# match.net
KiCad netlist of a schematic drawn in EAGLE
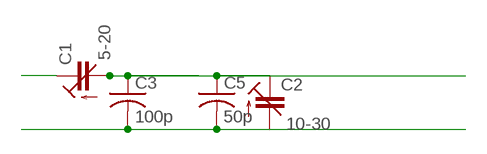
[diagram p0: schematic, sheet 1]

(export (version "E")
  (design (tool "Eeschema 10.0.6"))
  (components
    (comp (ref "C1")
      (value "5-20")
      (footprint "eagle-import:SGC3S")
      (libsource (lib "eagle-import") (part "C-TRIMM"))
    )
    (comp (ref "C2")
      (value "10-30")
      (footprint "eagle-import:SGC3S")
      (libsource (lib "eagle-import") (part "C-TRIMM"))
    )
    (comp (ref "C3")
      (value "100p")
      (footprint "eagle-import:C0805")
      (libsource (lib "eagle-import") (part "C-USC0805"))
    )
    (comp (ref "C5")
      (value "50p")
      (footprint "eagle-import:C0805")
      (libsource (lib "eagle-import") (part "C-USC0805"))
    )
  )
  (nets
    (net (code "1") (name "Net-(C1-A)") (class "Default")
      (node (ref "C1") (pin "P$1") (pinfunction "A_P$1") (pintype "passive"))
      (node (ref "C2") (pin "P$2") (pinfunction "E_P$2") (pintype "passive"))
      (node (ref "C3") (pin "1") (pinfunction "1_1") (pintype "passive"))
      (node (ref "C5") (pin "1") (pinfunction "1_1") (pintype "passive"))
    )
    (net (code "2") (name "Net-(C3-Pad2)") (class "Default")
      (node (ref "C3") (pin "2") (pinfunction "2_2") (pintype "passive"))
      (node (ref "C5") (pin "2") (pinfunction "2_2") (pintype "passive"))
    )
    (net (code "3") (name "unconnected-(C1-E-PadP$2)") (class "Default")
      (node (ref "C1") (pin "P$2") (pinfunction "E_P$2") (pintype "passive"))
    )
    (net (code "4") (name "unconnected-(C2-A-PadP$1)") (class "Default")
      (node (ref "C2") (pin "P$1") (pinfunction "A_P$1") (pintype "passive"))
    )
  )
)
